# DetectHeat_Board.net
KiCad netlist of a schematic drawn in EAGLE
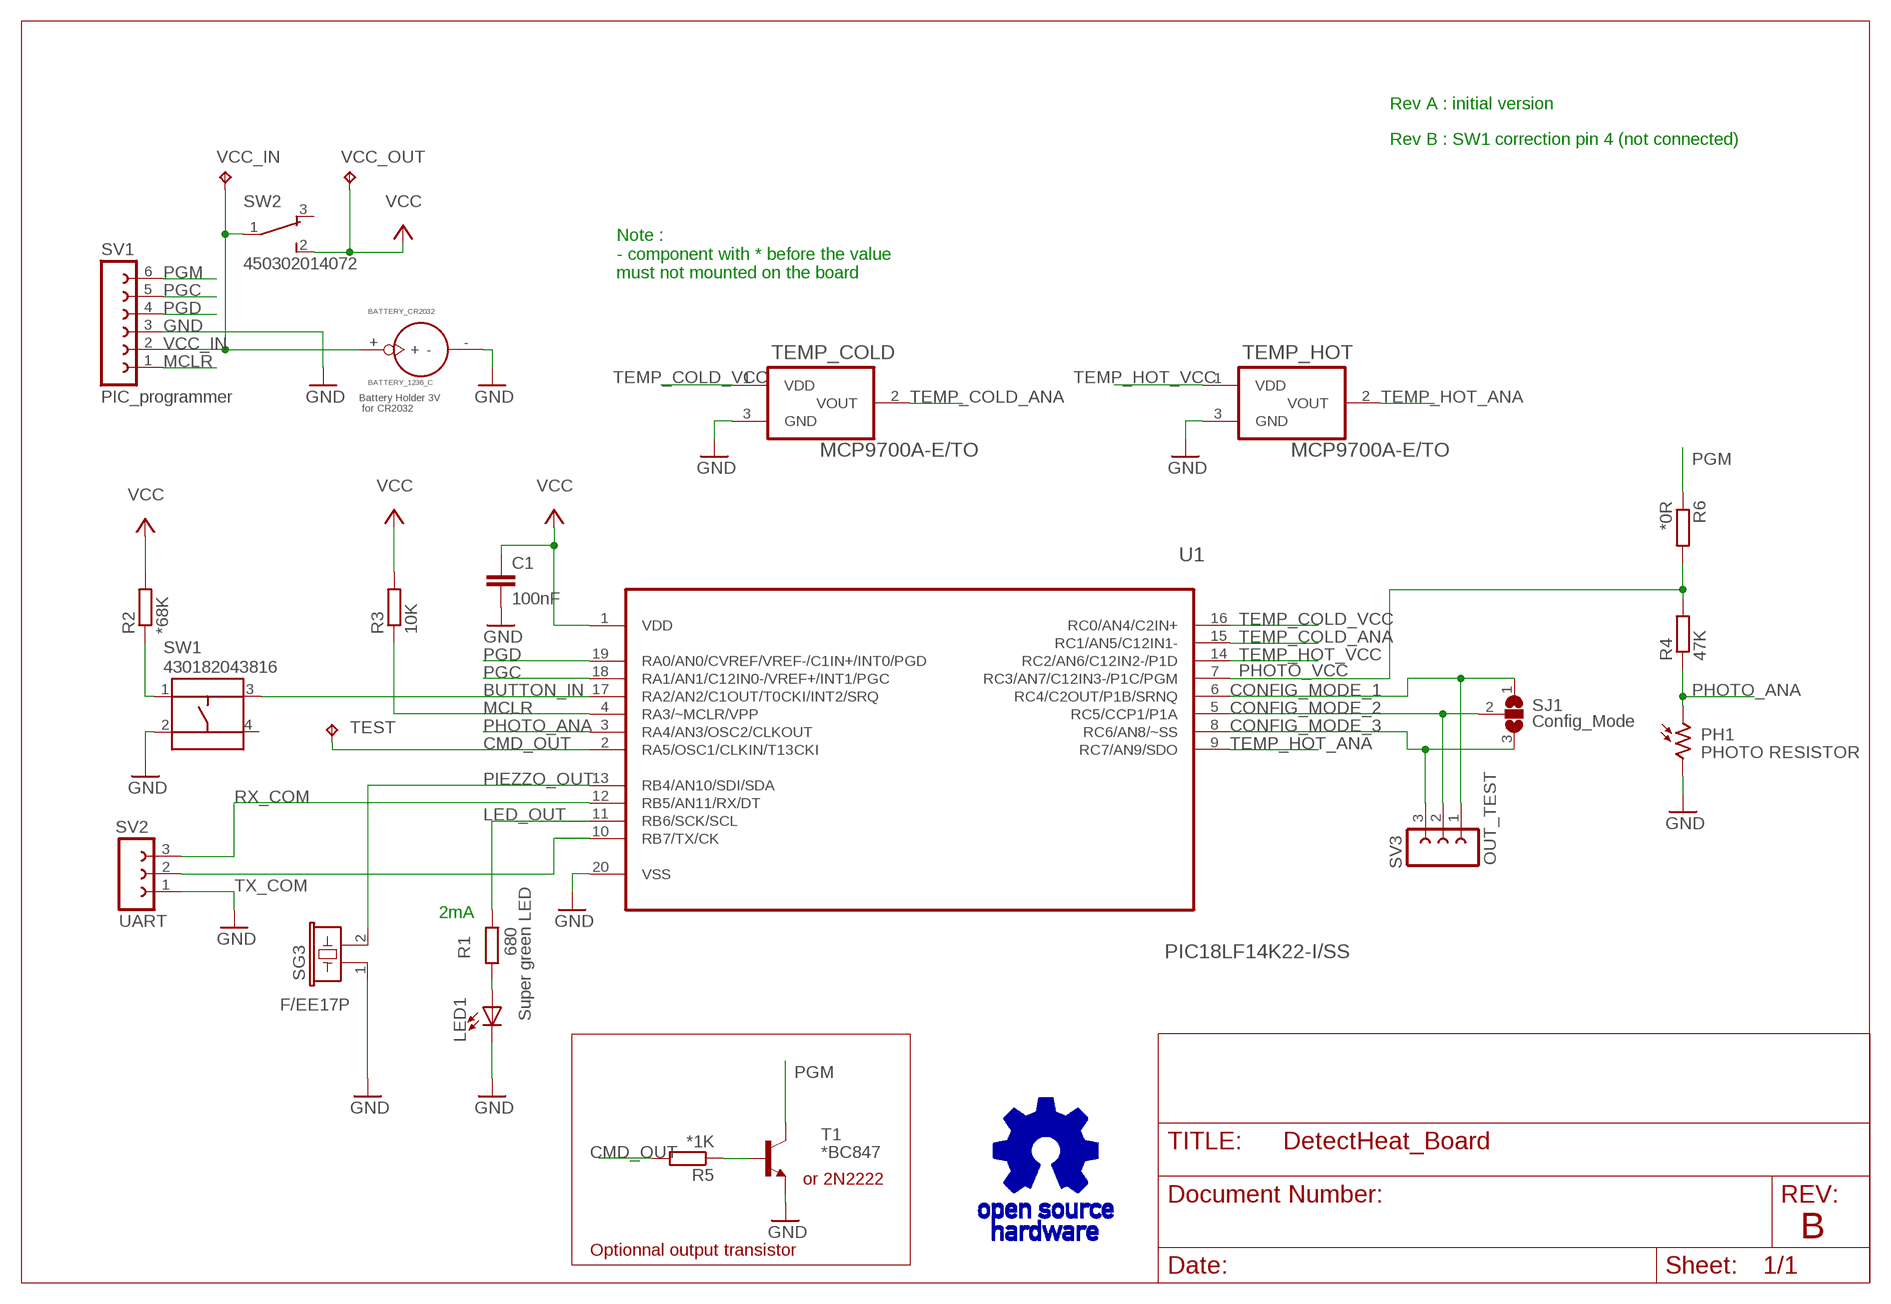
[diagram p0: schematic, sheet 1]

(export (version "E")
  (design (tool "Eeschema 10.0.6"))
  (components
    (comp (ref "BATTERY_CR2032")
      (value "BATTERY_1236_C")
      (footprint "eagle-import:BATTERY_1236_C")
      (libsource (lib "eagle-import") (part "BATTERY_1236_C"))
    )
    (comp (ref "C1")
      (value "100nF")
      (footprint "eagle-import:C0805")
      (libsource (lib "eagle-import") (part "C-EUC0805"))
    )
    (comp (ref "LED1")
      (value "Super green LED")
      (footprint "eagle-import:CHIPLED_0805")
      (libsource (lib "eagle-import") (part "LEDCHIPLED_0805"))
    )
    (comp (ref "PH1")
      (value "PHOTO RESISTOR")
      (footprint "eagle-import:T0-46-A10XX")
      (libsource (lib "eagle-import") (part "A1050_09"))
    )
    (comp (ref "R1")
      (value "680")
      (footprint "eagle-import:R0805")
      (libsource (lib "eagle-import") (part "R-EU_R0805"))
    )
    (comp (ref "R2")
      (value "*68K")
      (footprint "eagle-import:R0805")
      (libsource (lib "eagle-import") (part "R-EU_R0805"))
    )
    (comp (ref "R3")
      (value "10K")
      (footprint "eagle-import:R0805")
      (libsource (lib "eagle-import") (part "R-EU_R0805"))
    )
    (comp (ref "R4")
      (value "47K")
      (footprint "eagle-import:R0805")
      (libsource (lib "eagle-import") (part "R-EU_R0805"))
    )
    (comp (ref "R5")
      (value "*1K")
      (footprint "eagle-import:R0805")
      (libsource (lib "eagle-import") (part "R-EU_R0805"))
    )
    (comp (ref "R6")
      (value "*0R")
      (footprint "eagle-import:R0805")
      (libsource (lib "eagle-import") (part "R-EU_R0805"))
    )
    (comp (ref "SG3")
      (value "F/EE17P")
      (footprint "eagle-import:F_EE17P")
      (libsource (lib "eagle-import") (part "F/EE17P"))
    )
    (comp (ref "SJ1")
      (value "Config_Mode")
      (footprint "eagle-import:SJ_2")
      (libsource (lib "eagle-import") (part "SJ2W"))
    )
    (comp (ref "SV1")
      (value "PIC_programmer")
      (footprint "eagle-import:FE06")
      (libsource (lib "eagle-import") (part "FE06-1"))
    )
    (comp (ref "SV2")
      (value "UART")
      (footprint "eagle-import:FE03-1")
      (libsource (lib "eagle-import") (part "FE03-1"))
    )
    (comp (ref "SV3")
      (value "OUT_TEST")
      (footprint "eagle-import:FE03-1")
      (libsource (lib "eagle-import") (part "FE03-1"))
    )
    (comp (ref "SW1")
      (value "430182043816")
      (footprint "eagle-import:430182043816")
      (libsource (lib "eagle-import") (part "430182043816"))
    )
    (comp (ref "SW2")
      (value "450302014072")
      (footprint "eagle-import:450302014072")
      (libsource (lib "eagle-import") (part "450302014072"))
    )
    (comp (ref "T1")
      (value "*BC847")
      (footprint "eagle-import:SOT23")
      (libsource (lib "eagle-import") (part "BC847"))
    )
    (comp (ref "TEMP_COLD")
      (value "MCP9700A-E/TO")
      (footprint "eagle-import:TO127P254X533-3")
      (libsource (lib "eagle-import") (part "MCP9700A-E/TO"))
    )
    (comp (ref "TEMP_HOT")
      (value "MCP9700A-E/TO")
      (footprint "eagle-import:TO127P254X533-3")
      (libsource (lib "eagle-import") (part "MCP9700A-E/TO"))
    )
    (comp (ref "TEST")
      (value "TPPAD1-13")
      (footprint "eagle-import:P1-13")
      (libsource (lib "eagle-import") (part "TPPAD1-13"))
    )
    (comp (ref "U1")
      (value "PIC18LF14K22-I/SS")
      (footprint "eagle-import:SOP65P780X200-20N")
      (fields (field (name "MPN") "PIC18LF14k22-I/SS"))
      (libsource (lib "eagle-import") (part "PIC18LF14K22-I/SS"))
    )
    (comp (ref "VCC_IN")
      (value "TPPAD1-13")
      (footprint "eagle-import:P1-13")
      (libsource (lib "eagle-import") (part "TPPAD1-13"))
    )
    (comp (ref "VCC_OUT")
      (value "TPPAD1-13")
      (footprint "eagle-import:P1-13")
      (libsource (lib "eagle-import") (part "TPPAD1-13"))
    )
  )
  (nets
    (net (code "1") (name "/BUTTON_IN") (class "Default")
      (node (ref "SW1") (pin "3") (pinfunction "3_3") (pintype "bidirectional"))
      (node (ref "U1") (pin "17") (pinfunction "RA2/AN2/C1OUT/T0CKI/INT2/SRQ_17") (pintype "bidirectional"))
    )
    (net (code "2") (name "/CMD_OUT") (class "Default")
      (node (ref "R5") (pin "2") (pinfunction "2_2") (pintype "passive"))
      (node (ref "TEST") (pin "TP") (pinfunction "TP_TP") (pintype "input"))
      (node (ref "U1") (pin "2") (pinfunction "RA5/OSC1/CLKIN/T13CKI_2") (pintype "bidirectional"))
    )
    (net (code "3") (name "/CONFIG_MODE_1") (class "Default")
      (node (ref "SJ1") (pin "1") (pinfunction "1_1") (pintype "passive"))
      (node (ref "SV3") (pin "1") (pinfunction "1_1") (pintype "passive"))
      (node (ref "U1") (pin "6") (pinfunction "RC4/C2OUT/P1B/SRNQ_6") (pintype "bidirectional"))
    )
    (net (code "4") (name "/CONFIG_MODE_2") (class "Default")
      (node (ref "SJ1") (pin "2") (pinfunction "2_2") (pintype "passive"))
      (node (ref "SV3") (pin "2") (pinfunction "2_2") (pintype "passive"))
      (node (ref "U1") (pin "5") (pinfunction "RC5/CCP1/P1A_5") (pintype "bidirectional"))
    )
    (net (code "5") (name "/CONFIG_MODE_3") (class "Default")
      (node (ref "SJ1") (pin "3") (pinfunction "3_3") (pintype "passive"))
      (node (ref "SV3") (pin "3") (pinfunction "3_3") (pintype "passive"))
      (node (ref "U1") (pin "8") (pinfunction "RC6/AN8/~{SS}_8") (pintype "bidirectional"))
    )
    (net (code "6") (name "/LED_OUT") (class "Default")
      (node (ref "R1") (pin "1") (pinfunction "1_1") (pintype "passive"))
      (node (ref "U1") (pin "11") (pinfunction "RB6/SCK/SCL_11") (pintype "bidirectional"))
    )
    (net (code "7") (name "/MCLR") (class "Default")
      (node (ref "R3") (pin "1") (pinfunction "1_1") (pintype "passive"))
      (node (ref "SV1") (pin "1") (pinfunction "1_1") (pintype "passive"))
      (node (ref "U1") (pin "4") (pinfunction "RA3/~{MCLR/VPP}_4") (pintype "bidirectional"))
    )
    (net (code "8") (name "/PGC") (class "Default")
      (node (ref "SV1") (pin "5") (pinfunction "5_5") (pintype "passive"))
      (node (ref "U1") (pin "18") (pinfunction "RA1/AN1/C12IN0-/VREF+/INT1/PGC_18") (pintype "bidirectional"))
    )
    (net (code "9") (name "/PGD") (class "Default")
      (node (ref "SV1") (pin "4") (pinfunction "4_4") (pintype "passive"))
      (node (ref "U1") (pin "19") (pinfunction "RA0/AN0/CVREF/VREF-/C1IN+/INT0/PGD_19") (pintype "bidirectional"))
    )
    (net (code "10") (name "/PGM") (class "Default")
      (node (ref "R6") (pin "1") (pinfunction "1_1") (pintype "passive"))
      (node (ref "SV1") (pin "6") (pinfunction "6_6") (pintype "passive"))
      (node (ref "T1") (pin "3") (pinfunction "C_3") (pintype "passive"))
    )
    (net (code "11") (name "/PHOTO_ANA") (class "Default")
      (node (ref "PH1") (pin "1") (pinfunction "1_1") (pintype "passive"))
      (node (ref "R4") (pin "1") (pinfunction "1_1") (pintype "passive"))
      (node (ref "U1") (pin "3") (pinfunction "RA4/AN3/OSC2/CLKOUT_3") (pintype "bidirectional"))
    )
    (net (code "12") (name "/PHOTO_VCC") (class "Default")
      (node (ref "R4") (pin "2") (pinfunction "2_2") (pintype "passive"))
      (node (ref "R6") (pin "2") (pinfunction "2_2") (pintype "passive"))
      (node (ref "U1") (pin "7") (pinfunction "RC3/AN7/C12IN3-/P1C/PGM_7") (pintype "bidirectional"))
    )
    (net (code "13") (name "/PIEZZO_OUT") (class "Default")
      (node (ref "SG3") (pin "2") (pinfunction "2_2") (pintype "passive"))
      (node (ref "U1") (pin "13") (pinfunction "RB4/AN10/SDI/SDA_13") (pintype "bidirectional"))
    )
    (net (code "14") (name "/RX_COM") (class "Default")
      (node (ref "SV2") (pin "3") (pinfunction "3_3") (pintype "passive"))
      (node (ref "U1") (pin "12") (pinfunction "RB5/AN11/RX/DT_12") (pintype "bidirectional"))
    )
    (net (code "15") (name "/TEMP_COLD_ANA") (class "Default")
      (node (ref "TEMP_COLD") (pin "2") (pinfunction "VOUT_2") (pintype "output"))
      (node (ref "U1") (pin "15") (pinfunction "RC1/AN5/C12IN1-_15") (pintype "bidirectional"))
    )
    (net (code "16") (name "/TEMP_COLD_VCC") (class "Default")
      (node (ref "TEMP_COLD") (pin "1") (pinfunction "VDD_1") (pintype "power_in"))
      (node (ref "U1") (pin "16") (pinfunction "RC0/AN4/C2IN+_16") (pintype "bidirectional"))
    )
    (net (code "17") (name "/TEMP_HOT_ANA") (class "Default")
      (node (ref "TEMP_HOT") (pin "2") (pinfunction "VOUT_2") (pintype "output"))
      (node (ref "U1") (pin "9") (pinfunction "RC7/AN9/SDO_9") (pintype "bidirectional"))
    )
    (net (code "18") (name "/TEMP_HOT_VCC") (class "Default")
      (node (ref "TEMP_HOT") (pin "1") (pinfunction "VDD_1") (pintype "power_in"))
      (node (ref "U1") (pin "14") (pinfunction "RC2/AN6/C12IN2-/P1D_14") (pintype "bidirectional"))
    )
    (net (code "19") (name "/TX_COM") (class "Default")
      (node (ref "SV2") (pin "2") (pinfunction "2_2") (pintype "passive"))
      (node (ref "U1") (pin "10") (pinfunction "RB7/TX/CK_10") (pintype "bidirectional"))
    )
    (net (code "20") (name "/VCC_IN") (class "Default")
      (node (ref "BATTERY_CR2032") (pin "+") (pinfunction "+_+") (pintype "bidirectional"))
      (node (ref "SV1") (pin "2") (pinfunction "2_2") (pintype "passive"))
      (node (ref "SW2") (pin "1") (pinfunction "1_1") (pintype "passive"))
      (node (ref "VCC_IN") (pin "TP") (pinfunction "TP_TP") (pintype "input"))
    )
    (net (code "21") (name "GND") (class "Default")
      (node (ref "BATTERY_CR2032") (pin "-") (pinfunction "-_-") (pintype "bidirectional"))
      (node (ref "C1") (pin "2") (pinfunction "2_2") (pintype "passive"))
      (node (ref "LED1") (pin "C") (pinfunction "C_C") (pintype "passive"))
      (node (ref "PH1") (pin "2") (pinfunction "2_2") (pintype "passive"))
      (node (ref "SG3") (pin "1") (pinfunction "1_1") (pintype "passive"))
      (node (ref "SV1") (pin "3") (pinfunction "3_3") (pintype "passive"))
      (node (ref "SV2") (pin "1") (pinfunction "1_1") (pintype "passive"))
      (node (ref "SW1") (pin "2") (pinfunction "2_2") (pintype "bidirectional"))
      (node (ref "T1") (pin "2") (pinfunction "E_2") (pintype "passive"))
      (node (ref "TEMP_COLD") (pin "3") (pinfunction "GND_3") (pintype "passive"))
      (node (ref "TEMP_HOT") (pin "3") (pinfunction "GND_3") (pintype "passive"))
      (node (ref "U1") (pin "20") (pinfunction "VSS_20") (pintype "passive"))
    )
    (net (code "22") (name "Net-(LED1-PadA)") (class "Default")
      (node (ref "LED1") (pin "A") (pinfunction "A_A") (pintype "passive"))
      (node (ref "R1") (pin "2") (pinfunction "2_2") (pintype "passive"))
    )
    (net (code "23") (name "Net-(R2-Pad1)") (class "Default")
      (node (ref "R2") (pin "1") (pinfunction "1_1") (pintype "passive"))
      (node (ref "SW1") (pin "1") (pinfunction "1_1") (pintype "bidirectional"))
    )
    (net (code "24") (name "Net-(T1-B)") (class "Default")
      (node (ref "R5") (pin "1") (pinfunction "1_1") (pintype "passive"))
      (node (ref "T1") (pin "1") (pinfunction "B_1") (pintype "passive"))
    )
    (net (code "25") (name "VCC") (class "Default")
      (node (ref "C1") (pin "1") (pinfunction "1_1") (pintype "passive"))
      (node (ref "R2") (pin "2") (pinfunction "2_2") (pintype "passive"))
      (node (ref "R3") (pin "2") (pinfunction "2_2") (pintype "passive"))
      (node (ref "SW2") (pin "2") (pinfunction "2_2") (pintype "passive"))
      (node (ref "U1") (pin "1") (pinfunction "VDD_1") (pintype "power_in"))
      (node (ref "VCC_OUT") (pin "TP") (pinfunction "TP_TP") (pintype "input"))
    )
    (net (code "26") (name "unconnected-(SW1-Pad4)") (class "Default")
      (node (ref "SW1") (pin "4") (pinfunction "4_4") (pintype "bidirectional"))
    )
    (net (code "27") (name "unconnected-(SW2-Pad3)") (class "Default")
      (node (ref "SW2") (pin "3") (pinfunction "3_3") (pintype "passive"))
    )
  )
)
